# Lick_Sensor_module_v1_0.net
KiCad netlist of a schematic drawn in EAGLE
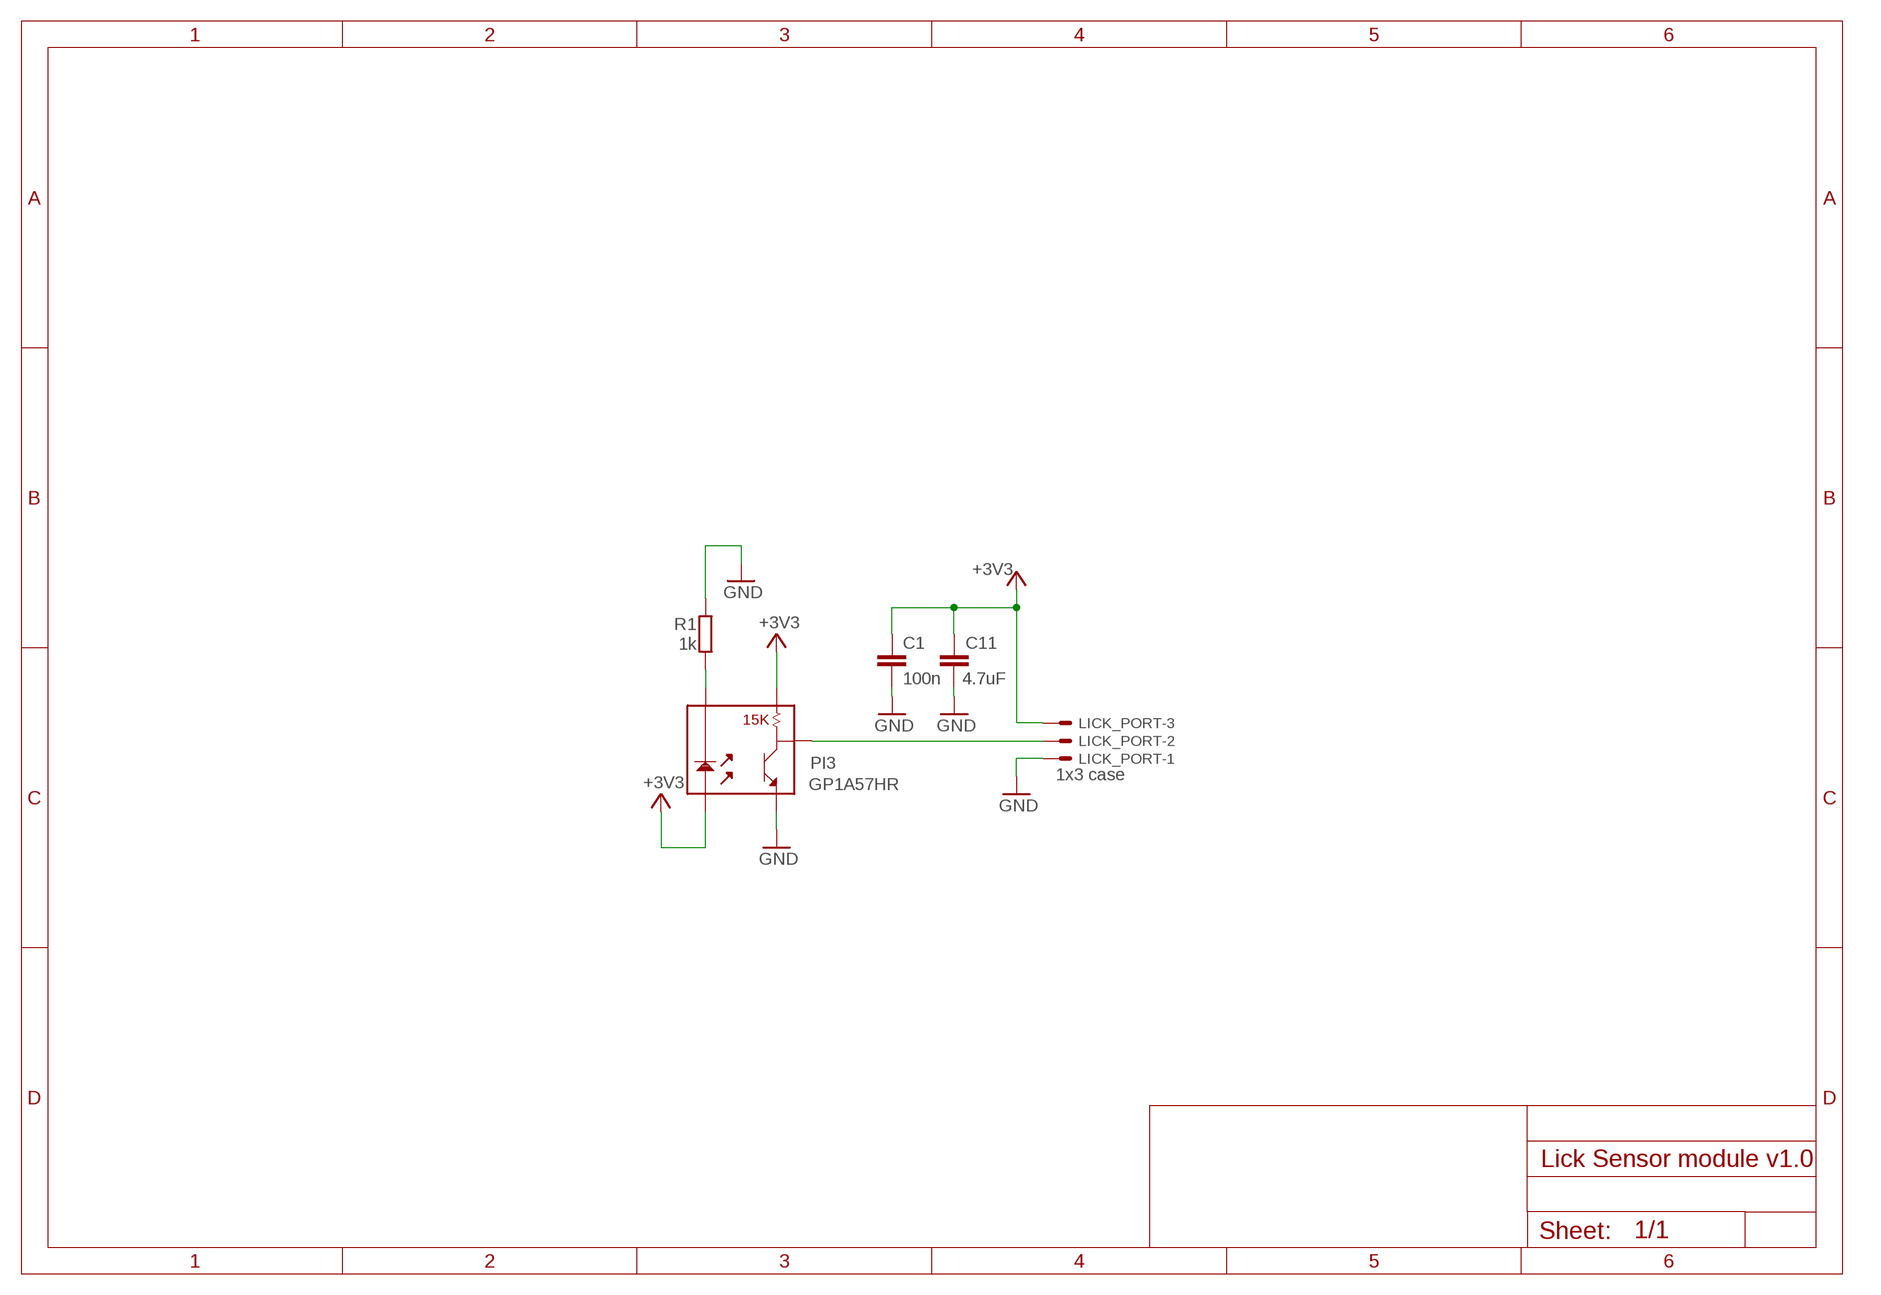
[diagram p0: schematic, sheet 1]

(export (version "E")
  (design (tool "Eeschema 10.0.6"))
  (components
    (comp (ref "C1")
      (value "100n")
      (footprint "eagle-import:C0402K")
      (fields (field (name "MPN") "GRM155R71E104KE14D"))
      (libsource (lib "eagle-import") (part "rcl_334_C-EUC0402K"))
    )
    (comp (ref "C11")
      (value "4.7uF")
      (footprint "eagle-import:C0603")
      (fields (field (name "MPN") "C1608X6S1C475K080AC"))
      (libsource (lib "eagle-import") (part "C-EUC0603"))
    )
    (comp (ref "LICK_PORT")
      (value "1x3 case")
      (footprint "eagle-import:22-23-2031")
      (fields
        (field (name "MF") "MOLEX")
        (field (name "MPN") "22-23-2031")
        (field (name "MPN_1") "282834-3")
        (field (name "OEPS") "OEPS070035")
      )
      (libsource (lib "eagle-import") (part "22-23-2031"))
    )
    (comp (ref "PI3")
      (value "GP1A57HR")
      (footprint "eagle-import:GP1A57HR")
      (description "SENSOR OPTICAL 10MM PCB MOUNT")
      (fields (field (name "MPN") "GP1A57HRJ00F"))
      (libsource (lib "eagle-import") (part "GP1A57HR"))
    )
    (comp (ref "R1")
      (value "1k")
      (footprint "eagle-import:R0603")
      (fields (field (name "MPN") "ERJ-2RKF1001X"))
      (libsource (lib "eagle-import") (part "R-EU_R0603"))
    )
  )
  (nets
    (net (code "1") (name "+3V3") (class "Default")
      (node (ref "C1") (pin "1") (pinfunction "1_1") (pintype "passive"))
      (node (ref "C11") (pin "1") (pinfunction "1_1") (pintype "passive"))
      (node (ref "LICK_PORT") (pin "3") (pinfunction "S_3") (pintype "passive"))
      (node (ref "PI3") (pin "1") (pinfunction "1_1") (pintype "bidirectional"))
      (node (ref "PI3") (pin "3") (pinfunction "3_3") (pintype "bidirectional"))
    )
    (net (code "2") (name "GND") (class "Default")
      (node (ref "C1") (pin "2") (pinfunction "2_2") (pintype "passive"))
      (node (ref "C11") (pin "2") (pinfunction "2_2") (pintype "passive"))
      (node (ref "LICK_PORT") (pin "1") (pinfunction "S_1") (pintype "passive"))
      (node (ref "PI3") (pin "5") (pinfunction "5_5") (pintype "bidirectional"))
      (node (ref "R1") (pin "2") (pinfunction "2_2") (pintype "passive"))
    )
    (net (code "3") (name "Net-(LICK_PORTB-S)") (class "Default")
      (node (ref "LICK_PORT") (pin "2") (pinfunction "S_2") (pintype "passive"))
      (node (ref "PI3") (pin "4") (pinfunction "4_4") (pintype "bidirectional"))
    )
    (net (code "4") (name "Net-(PI3-Pad2)") (class "Default")
      (node (ref "PI3") (pin "2") (pinfunction "2_2") (pintype "bidirectional"))
      (node (ref "R1") (pin "1") (pinfunction "1_1") (pintype "passive"))
    )
  )
)
